# Sheet1.net
KiCad netlist of a schematic drawn in Altium Designer
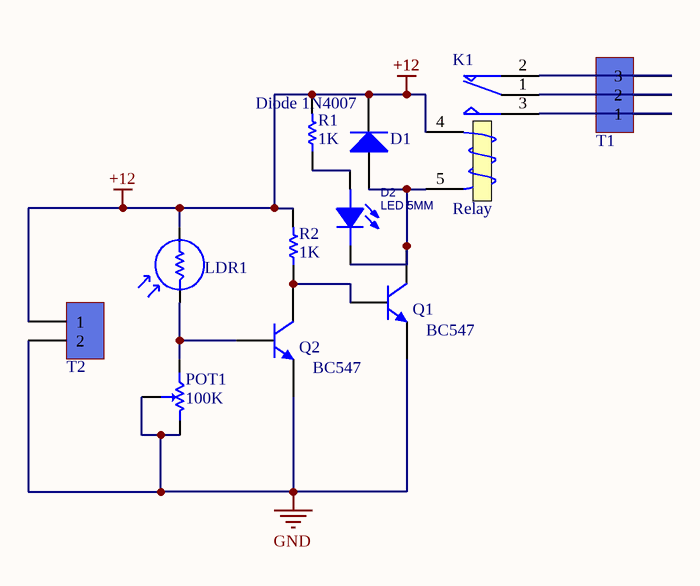
[diagram p0: Sheet1.SchDoc]

(export (version "E")
  (design (tool "Eeschema 10.0.6"))
  (components
    (comp (ref "D1")
      (value "Diode 1N4007")
      (footprint "DO-41")
      (description "1 Amp General Purpose Rectifier")
      (fields (field (name "PUBLISHER") "Altium Limited"))
      (libsource (lib "Miscellaneous Devices") (part "Diode 1N4007"))
    )
    (comp (ref "D2")
      (value "LED 5MM")
      (footprint "LED5MM_BLUE")
      (description "Light Emitting Diode")
      (fields (field (name "DESIGNER") "Abbas Basereh"))
      (libsource (lib "Altium") (part "LED 5MM"))
    )
    (comp (ref "K1")
      (value "Relay")
      (footprint "Relay 15.40x12.10x13.10")
      (description "Relay_SPDT POWER NEEDLE")
      (fields (field (name "DESIGNER") "Ali Hafizi"))
      (libsource (lib "Altium") (part "RELAY General"))
    )
    (comp (ref "LDR1")
      (value "PhotoCell")
      (footprint "PhotoCell")
      (description "Photo Cell- Variable Resistor With Light")
      (fields (field (name "DESIGNER") "Saeid Jorablo"))
      (libsource (lib "Altium") (part "LDR"))
    )
    (comp (ref "POT1")
      (value "100K")
      (footprint "POT")
      (description "Variable Resistor")
      (libsource (lib "Altium") (part "POT"))
    )
    (comp (ref "Q1")
      (value "BC547")
      (footprint "TO-92 STR")
      (description "NPN General-purpose Transistor")
      (fields (field (name "DESIGNER") "Abbas Basereh"))
      (libsource (lib "Altium") (part "BC547"))
    )
    (comp (ref "Q2")
      (value "BC547")
      (footprint "TO-92 STR")
      (description "NPN General-purpose Transistor")
      (fields (field (name "DESIGNER") "Abbas Basereh"))
      (libsource (lib "Altium") (part "BC547"))
    )
    (comp (ref "R1")
      (value "1K")
      (footprint "RES-(1/4)")
      (description "TOTAL DIP RESISTOR PACK")
      (fields (field (name "DESIGNER") "Ali Hafizi"))
      (libsource (lib "Altium") (part "RES DIP PACKAGE"))
    )
    (comp (ref "R2")
      (value "1K")
      (footprint "RES-(1/4)")
      (description "TOTAL DIP RESISTOR PACK")
      (fields (field (name "DESIGNER") "Ali Hafizi"))
      (libsource (lib "Altium") (part "RES DIP PACKAGE"))
    )
    (comp (ref "T1")
      (value "Terminal")
      (footprint "Terminal 1*3")
      (description "Terminal 3 Pin 250VAC 16A")
      (fields (field (name "DESIGNER") "Seyed Mohsen Ghasemain") (field (name "E-MAIL") "picpars@gmail.com"))
      (libsource (lib "usefully_Library") (part "Terminal 1*3"))
    )
    (comp (ref "T2")
      (value "Terminal")
      (footprint "Terminal 1*2")
      (description "Terminal 2 Pin 250VAC 16A")
      (fields (field (name "DESIGNER") "Seyed Mohsen Ghasemain") (field (name "E-MAIL") "picpars@gmail.com"))
      (libsource (lib "usefully_Library") (part "Terminal 1*2"))
    )
  )
  (nets
    (net (code "1") (name "+12") (class "Default")
      (node (ref "D1") (pin "2") (pinfunction "K_2") (pintype "passive"))
      (node (ref "K1") (pin "4") (pinfunction "T1_4") (pintype "passive"))
      (node (ref "LDR1") (pin "2") (pintype "passive"))
      (node (ref "R1") (pin "2") (pinfunction "2_2") (pintype "passive"))
      (node (ref "R2") (pin "2") (pinfunction "2_2") (pintype "passive"))
      (node (ref "T2") (pin "1") (pinfunction "1_1") (pintype "passive"))
    )
    (net (code "2") (name "GND") (class "Default")
      (node (ref "POT1") (pin "2") (pinfunction "CW_2") (pintype "passive"))
      (node (ref "POT1") (pin "3") (pinfunction "SetPoint_3") (pintype "passive"))
      (node (ref "Q1") (pin "3") (pinfunction "E_3") (pintype "passive"))
      (node (ref "Q2") (pin "3") (pinfunction "E_3") (pintype "passive"))
      (node (ref "T2") (pin "2") (pinfunction "2_2") (pintype "passive"))
    )
    (net (code "3") (name "Net-(D1-A)") (class "Default")
      (node (ref "D1") (pin "1") (pinfunction "A_1") (pintype "passive"))
      (node (ref "D2") (pin "2") (pinfunction "CATHODE_2") (pintype "passive"))
      (node (ref "K1") (pin "5") (pinfunction "T2_5") (pintype "passive"))
      (node (ref "Q1") (pin "1") (pinfunction "C_1") (pintype "passive"))
    )
    (net (code "4") (name "Net-(D2-ANODE)") (class "Default")
      (node (ref "D2") (pin "1") (pinfunction "ANODE_1") (pintype "passive"))
      (node (ref "R1") (pin "1") (pinfunction "1_1") (pintype "passive"))
    )
    (net (code "5") (name "Net-(K1-COM)") (class "Default")
      (node (ref "K1") (pin "1") (pinfunction "COM_1") (pintype "passive"))
      (node (ref "T1") (pin "2") (pinfunction "2_2") (pintype "passive"))
    )
    (net (code "6") (name "Net-(K1-NC)") (class "Default")
      (node (ref "K1") (pin "2") (pinfunction "NC_2") (pintype "passive"))
      (node (ref "T1") (pin "3") (pinfunction "3_3") (pintype "passive"))
    )
    (net (code "7") (name "Net-(K1-NO)") (class "Default")
      (node (ref "K1") (pin "3") (pinfunction "NO_3") (pintype "passive"))
      (node (ref "T1") (pin "1") (pinfunction "1_1") (pintype "passive"))
    )
    (net (code "8") (name "Net-(POT1-CCW)") (class "Default")
      (node (ref "LDR1") (pin "1") (pintype "passive"))
      (node (ref "POT1") (pin "1") (pinfunction "CCW_1") (pintype "passive"))
      (node (ref "Q2") (pin "2") (pinfunction "B_2") (pintype "passive"))
    )
    (net (code "9") (name "Net-(Q1-B)") (class "Default")
      (node (ref "Q1") (pin "2") (pinfunction "B_2") (pintype "passive"))
      (node (ref "Q2") (pin "1") (pinfunction "C_1") (pintype "passive"))
      (node (ref "R2") (pin "1") (pinfunction "1_1") (pintype "passive"))
    )
  )
)
